# QCopterFC_USB_Sch.net
KiCad netlist of a schematic drawn in Altium Designer
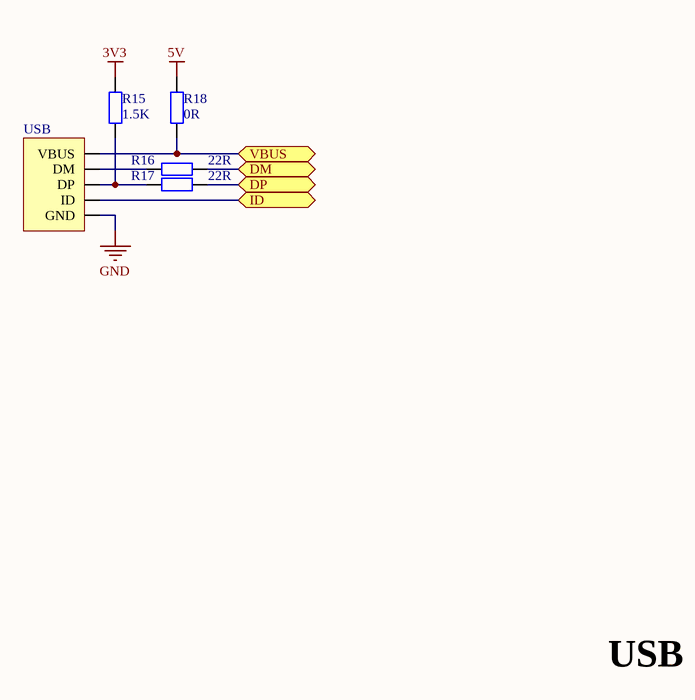
[diagram p0: QCopterFC_USB_Sch.SchDoc]

(export (version "E")
  (design (tool "Eeschema 10.0.6"))
  (components
    (comp (ref "R15")
      (value "1.5K")
      (footprint "PCB_Passive:RES_0603")
      (description "Resistor")
      (fields (field (name "Comment") "Res_0603"))
      (libsource (lib "") (part "Res_0603_1"))
    )
    (comp (ref "R16")
      (value "22R")
      (footprint "PCB_Passive:RES_0603")
      (description "Resistor")
      (fields (field (name "Comment") "Res_0603"))
      (libsource (lib "SCH_Passive") (part "Res_0603"))
    )
    (comp (ref "R17")
      (value "22R")
      (footprint "PCB_Passive:RES_0603")
      (description "Resistor")
      (fields (field (name "Comment") "Res_0603"))
      (libsource (lib "SCH_Passive") (part "Res_0603"))
    )
    (comp (ref "R18")
      (value "0R")
      (footprint "PCB_Passive:RES_0603")
      (description "Resistor")
      (fields (field (name "Comment") "Res_0603"))
      (libsource (lib "") (part "Res_0603_2"))
    )
    (comp (ref "USB")
      (value "USB_Micro")
      (footprint "PCB_USB:USB_MICRO_B")
      (description "USB")
      (libsource (lib "SCH_USB") (part "USB_Micro"))
    )
  )
  (nets
    (net (code "1") (name "/DM") (class "Default")
      (node (ref "R16") (pin "2") (pinfunction "2_2") (pintype "passive"))
    )
    (net (code "2") (name "/DP") (class "Default")
      (node (ref "R17") (pin "2") (pinfunction "2_2") (pintype "passive"))
    )
    (net (code "3") (name "/ID") (class "Default")
      (node (ref "USB") (pin "4") (pinfunction "ID_4") (pintype "passive"))
    )
    (net (code "4") (name "/VBUS") (class "Default")
      (node (ref "R18") (pin "2") (pinfunction "2_2") (pintype "passive"))
      (node (ref "USB") (pin "1") (pinfunction "VBUS_1") (pintype "passive"))
    )
    (net (code "5") (name "3V3") (class "Default")
      (node (ref "R15") (pin "2") (pinfunction "2_2") (pintype "passive"))
    )
    (net (code "6") (name "5V") (class "Default")
      (node (ref "R18") (pin "1") (pinfunction "1_1") (pintype "passive"))
    )
    (net (code "7") (name "GND") (class "Default")
      (node (ref "USB") (pin "5") (pinfunction "GND_5") (pintype "passive"))
    )
    (net (code "8") (name "Net-(USB-DM)") (class "Default")
      (node (ref "R16") (pin "1") (pinfunction "1_1") (pintype "passive"))
      (node (ref "USB") (pin "2") (pinfunction "DM_2") (pintype "passive"))
    )
    (net (code "9") (name "Net-(USB-DP)") (class "Default")
      (node (ref "R15") (pin "1") (pinfunction "1_1") (pintype "passive"))
      (node (ref "R17") (pin "1") (pinfunction "1_1") (pintype "passive"))
      (node (ref "USB") (pin "3") (pinfunction "DP_3") (pintype "passive"))
    )
  )
)
